# SRC_1_0.net
KiCad netlist of a schematic drawn in EAGLE
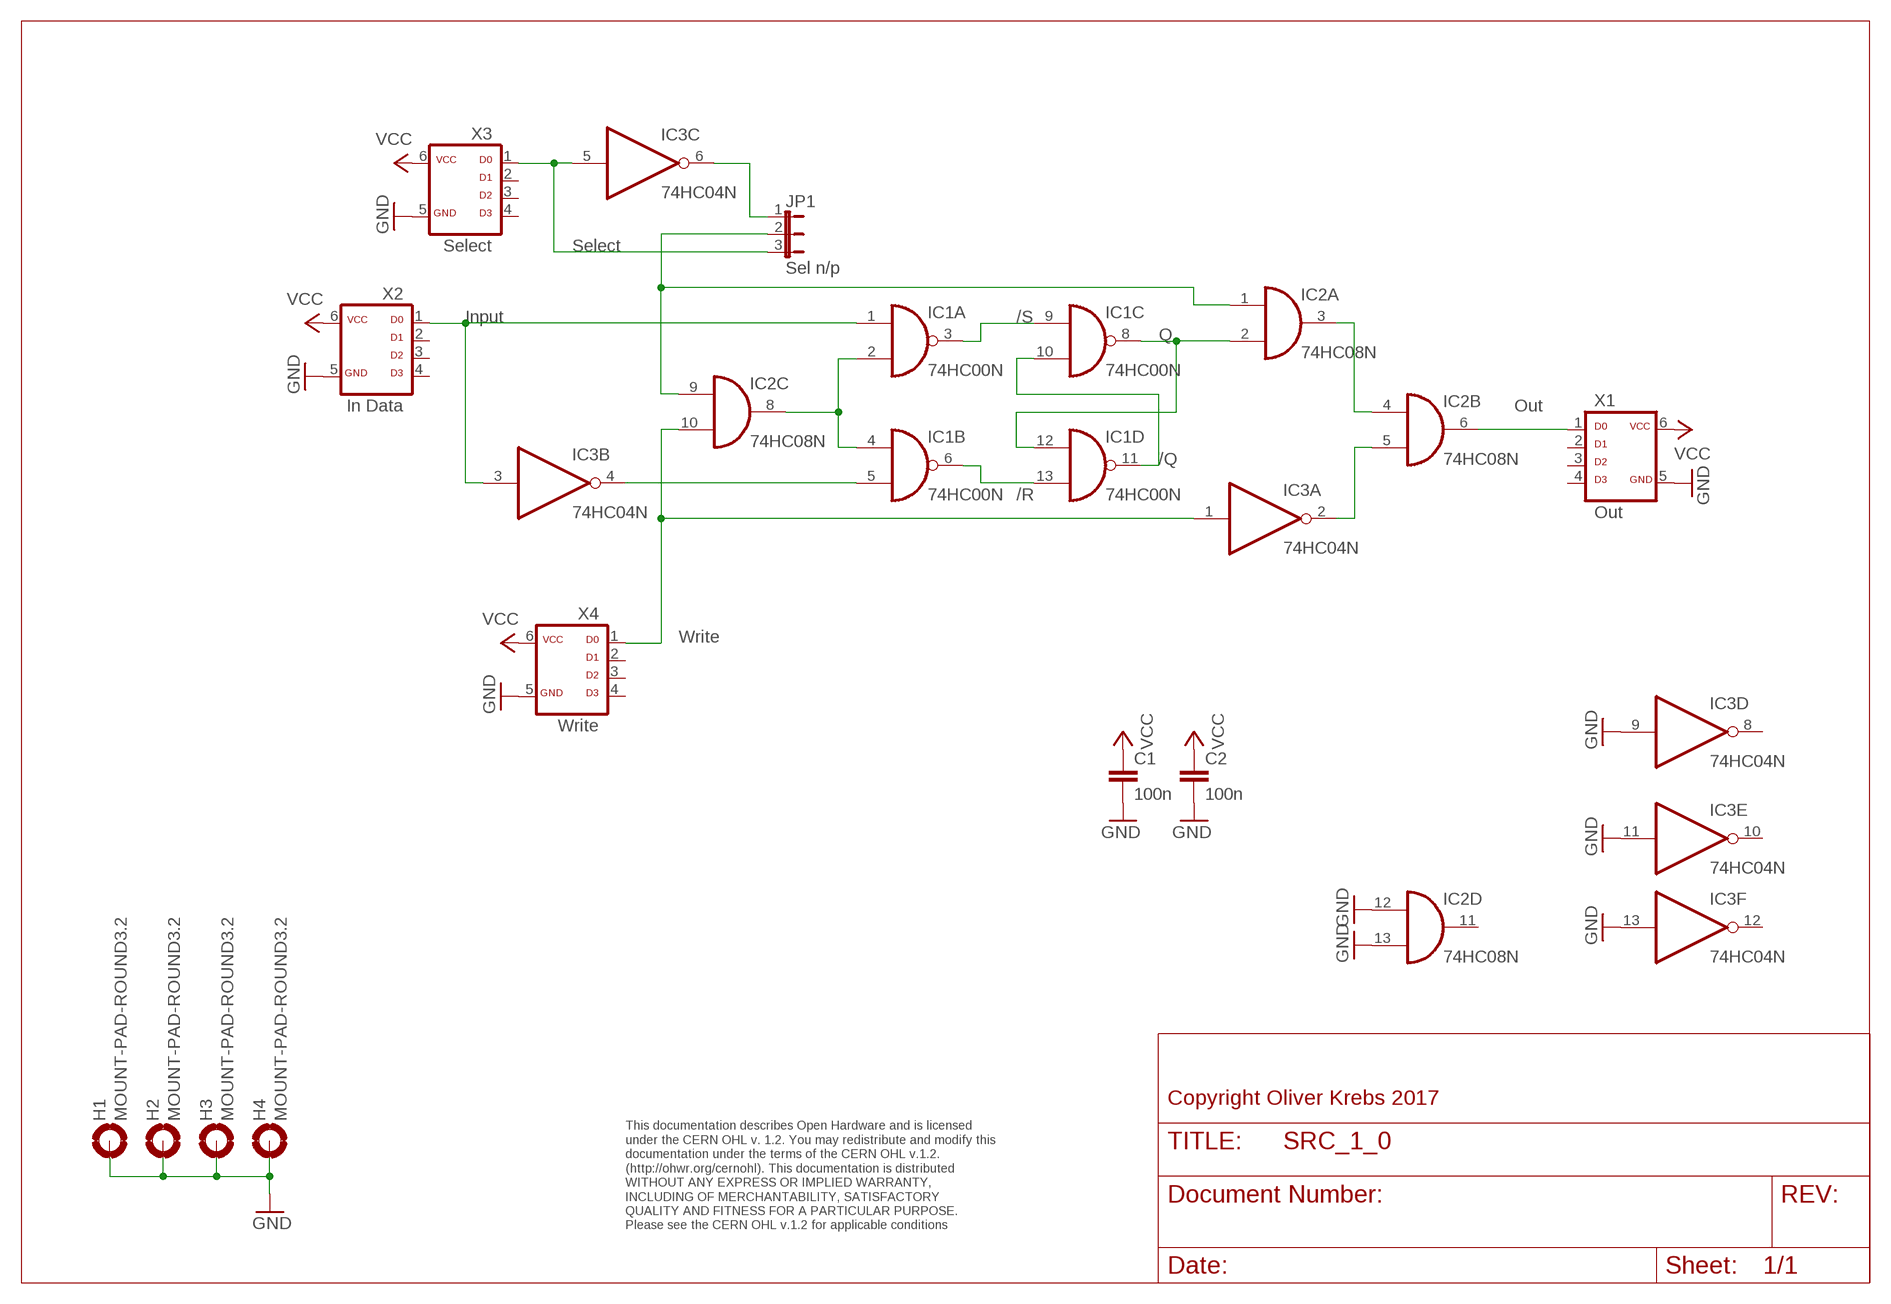
[diagram p0: schematic, sheet 1]

(export (version "E")
  (design (tool "Eeschema 10.0.6"))
  (components
    (comp (ref "C1")
      (value "100n")
      (footprint "eagle-import:C050-030X075")
      (libsource (lib "eagle-import") (part "C-EU050-030X075"))
    )
    (comp (ref "C2")
      (value "100n")
      (footprint "eagle-import:C050-030X075")
      (libsource (lib "eagle-import") (part "C-EU050-030X075"))
    )
    (comp (ref "H1")
      (value "MOUNT-PAD-ROUND3.2")
      (footprint "eagle-import:3,2-PAD")
      (libsource (lib "eagle-import") (part "MOUNT-PAD-ROUND3.2"))
    )
    (comp (ref "H2")
      (value "MOUNT-PAD-ROUND3.2")
      (footprint "eagle-import:3,2-PAD")
      (libsource (lib "eagle-import") (part "MOUNT-PAD-ROUND3.2"))
    )
    (comp (ref "H3")
      (value "MOUNT-PAD-ROUND3.2")
      (footprint "eagle-import:3,2-PAD")
      (libsource (lib "eagle-import") (part "MOUNT-PAD-ROUND3.2"))
    )
    (comp (ref "H4")
      (value "MOUNT-PAD-ROUND3.2")
      (footprint "eagle-import:3,2-PAD")
      (libsource (lib "eagle-import") (part "MOUNT-PAD-ROUND3.2"))
    )
    (comp (ref "IC1")
      (value "74HC00N")
      (footprint "eagle-import:DIL14")
      (libsource (lib "eagle-import") (part "7400NHC"))
    )
    (comp (ref "IC2")
      (value "74HC08N")
      (footprint "eagle-import:DIL14")
      (libsource (lib "eagle-import") (part "7408NHC"))
    )
    (comp (ref "IC3")
      (value "74HC04N")
      (footprint "eagle-import:DIL14")
      (libsource (lib "eagle-import") (part "7404NHC"))
    )
    (comp (ref "JP1")
      (value "Sel n/p")
      (footprint "eagle-import:JP2-U")
      (libsource (lib "eagle-import") (part "JP2EJP2-U"))
    )
    (comp (ref "X1")
      (value "Out")
      (footprint "eagle-import:ML-6")
      (libsource (lib "eagle-import") (part "ML6D"))
    )
    (comp (ref "X2")
      (value "In Data")
      (footprint "eagle-import:ML-6")
      (libsource (lib "eagle-import") (part "ML6D"))
    )
    (comp (ref "X3")
      (value "Select")
      (footprint "eagle-import:ML-6")
      (libsource (lib "eagle-import") (part "ML6D"))
    )
    (comp (ref "X4")
      (value "Write")
      (footprint "eagle-import:ML-6")
      (libsource (lib "eagle-import") (part "ML6D"))
    )
  )
  (nets
    (net (code "1") (name "GND") (class "Default")
      (node (ref "C1") (pin "2") (pinfunction "2_2") (pintype "passive"))
      (node (ref "C2") (pin "2") (pinfunction "2_2") (pintype "passive"))
      (node (ref "H1") (pin "B3,2") (pinfunction "MOUNT_B3,2") (pintype "passive"))
      (node (ref "H2") (pin "B3,2") (pinfunction "MOUNT_B3,2") (pintype "passive"))
      (node (ref "H3") (pin "B3,2") (pinfunction "MOUNT_B3,2") (pintype "passive"))
      (node (ref "H4") (pin "B3,2") (pinfunction "MOUNT_B3,2") (pintype "passive"))
      (node (ref "IC2") (pin "12") (pinfunction "I0_12") (pintype "input"))
      (node (ref "IC2") (pin "13") (pinfunction "I1_13") (pintype "input"))
      (node (ref "IC3") (pin "11") (pinfunction "I_11") (pintype "input"))
      (node (ref "IC3") (pin "13") (pinfunction "I_13") (pintype "input"))
      (node (ref "IC3") (pin "9") (pinfunction "I_9") (pintype "input"))
      (node (ref "X1") (pin "5") (pinfunction "5_5") (pintype "passive"))
      (node (ref "X2") (pin "5") (pinfunction "5_5") (pintype "passive"))
      (node (ref "X3") (pin "5") (pinfunction "5_5") (pintype "passive"))
      (node (ref "X4") (pin "5") (pinfunction "5_5") (pintype "passive"))
    )
    (net (code "2") (name "Net-(IC1A-I0)") (class "Default")
      (node (ref "IC1") (pin "1") (pinfunction "I0_1") (pintype "input"))
      (node (ref "IC3") (pin "3") (pinfunction "I_3") (pintype "input"))
      (node (ref "X2") (pin "1") (pinfunction "1_1") (pintype "passive"))
    )
    (net (code "3") (name "Net-(IC1A-I1)") (class "Default")
      (node (ref "IC1") (pin "2") (pinfunction "I1_2") (pintype "input"))
      (node (ref "IC1") (pin "4") (pinfunction "I0_4") (pintype "input"))
      (node (ref "IC2") (pin "8") (pinfunction "O_8") (pintype "output"))
    )
    (net (code "4") (name "Net-(IC1A-O)") (class "Default")
      (node (ref "IC1") (pin "3") (pinfunction "O_3") (pintype "output"))
      (node (ref "IC1") (pin "9") (pinfunction "I0_9") (pintype "input"))
    )
    (net (code "5") (name "Net-(IC1B-I1)") (class "Default")
      (node (ref "IC1") (pin "5") (pinfunction "I1_5") (pintype "input"))
      (node (ref "IC3") (pin "4") (pinfunction "O_4") (pintype "output"))
    )
    (net (code "6") (name "Net-(IC1B-O)") (class "Default")
      (node (ref "IC1") (pin "13") (pinfunction "I1_13") (pintype "input"))
      (node (ref "IC1") (pin "6") (pinfunction "O_6") (pintype "output"))
    )
    (net (code "7") (name "Net-(IC1C-I1)") (class "Default")
      (node (ref "IC1") (pin "10") (pinfunction "I1_10") (pintype "input"))
      (node (ref "IC1") (pin "11") (pinfunction "O_11") (pintype "output"))
    )
    (net (code "8") (name "Net-(IC1C-O)") (class "Default")
      (node (ref "IC1") (pin "12") (pinfunction "I0_12") (pintype "input"))
      (node (ref "IC1") (pin "8") (pinfunction "O_8") (pintype "output"))
      (node (ref "IC2") (pin "2") (pinfunction "I1_2") (pintype "input"))
    )
    (net (code "9") (name "Net-(IC2A-I0)") (class "Default")
      (node (ref "IC2") (pin "1") (pinfunction "I0_1") (pintype "input"))
      (node (ref "IC2") (pin "9") (pinfunction "I0_9") (pintype "input"))
      (node (ref "JP1") (pin "2") (pinfunction "2_2") (pintype "passive"))
    )
    (net (code "10") (name "Net-(IC2A-O)") (class "Default")
      (node (ref "IC2") (pin "3") (pinfunction "O_3") (pintype "output"))
      (node (ref "IC2") (pin "4") (pinfunction "I0_4") (pintype "input"))
    )
    (net (code "11") (name "Net-(IC2B-I1)") (class "Default")
      (node (ref "IC2") (pin "5") (pinfunction "I1_5") (pintype "input"))
      (node (ref "IC3") (pin "2") (pinfunction "O_2") (pintype "output"))
    )
    (net (code "12") (name "Net-(IC2B-O)") (class "Default")
      (node (ref "IC2") (pin "6") (pinfunction "O_6") (pintype "output"))
      (node (ref "X1") (pin "1") (pinfunction "1_1") (pintype "passive"))
    )
    (net (code "13") (name "Net-(IC2C-I1)") (class "Default")
      (node (ref "IC2") (pin "10") (pinfunction "I1_10") (pintype "input"))
      (node (ref "IC3") (pin "1") (pinfunction "I_1") (pintype "input"))
      (node (ref "X4") (pin "1") (pinfunction "1_1") (pintype "passive"))
    )
    (net (code "14") (name "Net-(IC3C-I)") (class "Default")
      (node (ref "IC3") (pin "5") (pinfunction "I_5") (pintype "input"))
      (node (ref "JP1") (pin "3") (pinfunction "3_3") (pintype "passive"))
      (node (ref "X3") (pin "1") (pinfunction "1_1") (pintype "passive"))
    )
    (net (code "15") (name "Net-(IC3C-O)") (class "Default")
      (node (ref "IC3") (pin "6") (pinfunction "O_6") (pintype "output"))
      (node (ref "JP1") (pin "1") (pinfunction "1_1") (pintype "passive"))
    )
    (net (code "16") (name "VCC") (class "Default")
      (node (ref "C1") (pin "1") (pinfunction "1_1") (pintype "passive"))
      (node (ref "C2") (pin "1") (pinfunction "1_1") (pintype "passive"))
      (node (ref "X1") (pin "6") (pinfunction "6_6") (pintype "passive"))
      (node (ref "X2") (pin "6") (pinfunction "6_6") (pintype "passive"))
      (node (ref "X3") (pin "6") (pinfunction "6_6") (pintype "passive"))
      (node (ref "X4") (pin "6") (pinfunction "6_6") (pintype "passive"))
    )
    (net (code "17") (name "unconnected-(IC2D-O-Pad11)") (class "Default")
      (node (ref "IC2") (pin "11") (pinfunction "O_11") (pintype "output"))
    )
    (net (code "18") (name "unconnected-(IC3D-O-Pad8)") (class "Default")
      (node (ref "IC3") (pin "8") (pinfunction "O_8") (pintype "output"))
    )
    (net (code "19") (name "unconnected-(IC3E-O-Pad10)") (class "Default")
      (node (ref "IC3") (pin "10") (pinfunction "O_10") (pintype "output"))
    )
    (net (code "20") (name "unconnected-(IC3F-O-Pad12)") (class "Default")
      (node (ref "IC3") (pin "12") (pinfunction "O_12") (pintype "output"))
    )
    (net (code "21") (name "unconnected-(X1-Pad2)") (class "Default")
      (node (ref "X1") (pin "2") (pinfunction "2_2") (pintype "passive"))
    )
    (net (code "22") (name "unconnected-(X1-Pad3)") (class "Default")
      (node (ref "X1") (pin "3") (pinfunction "3_3") (pintype "passive"))
    )
    (net (code "23") (name "unconnected-(X1-Pad4)") (class "Default")
      (node (ref "X1") (pin "4") (pinfunction "4_4") (pintype "passive"))
    )
    (net (code "24") (name "unconnected-(X2-Pad2)") (class "Default")
      (node (ref "X2") (pin "2") (pinfunction "2_2") (pintype "passive"))
    )
    (net (code "25") (name "unconnected-(X2-Pad3)") (class "Default")
      (node (ref "X2") (pin "3") (pinfunction "3_3") (pintype "passive"))
    )
    (net (code "26") (name "unconnected-(X2-Pad4)") (class "Default")
      (node (ref "X2") (pin "4") (pinfunction "4_4") (pintype "passive"))
    )
    (net (code "27") (name "unconnected-(X3-Pad2)") (class "Default")
      (node (ref "X3") (pin "2") (pinfunction "2_2") (pintype "passive"))
    )
    (net (code "28") (name "unconnected-(X3-Pad3)") (class "Default")
      (node (ref "X3") (pin "3") (pinfunction "3_3") (pintype "passive"))
    )
    (net (code "29") (name "unconnected-(X3-Pad4)") (class "Default")
      (node (ref "X3") (pin "4") (pinfunction "4_4") (pintype "passive"))
    )
    (net (code "30") (name "unconnected-(X4-Pad2)") (class "Default")
      (node (ref "X4") (pin "2") (pinfunction "2_2") (pintype "passive"))
    )
    (net (code "31") (name "unconnected-(X4-Pad3)") (class "Default")
      (node (ref "X4") (pin "3") (pinfunction "3_3") (pintype "passive"))
    )
    (net (code "32") (name "unconnected-(X4-Pad4)") (class "Default")
      (node (ref "X4") (pin "4") (pinfunction "4_4") (pintype "passive"))
    )
  )
)
